# zxld383-boost-driver-mk-4_0.net
KiCad netlist of a schematic drawn in EAGLE
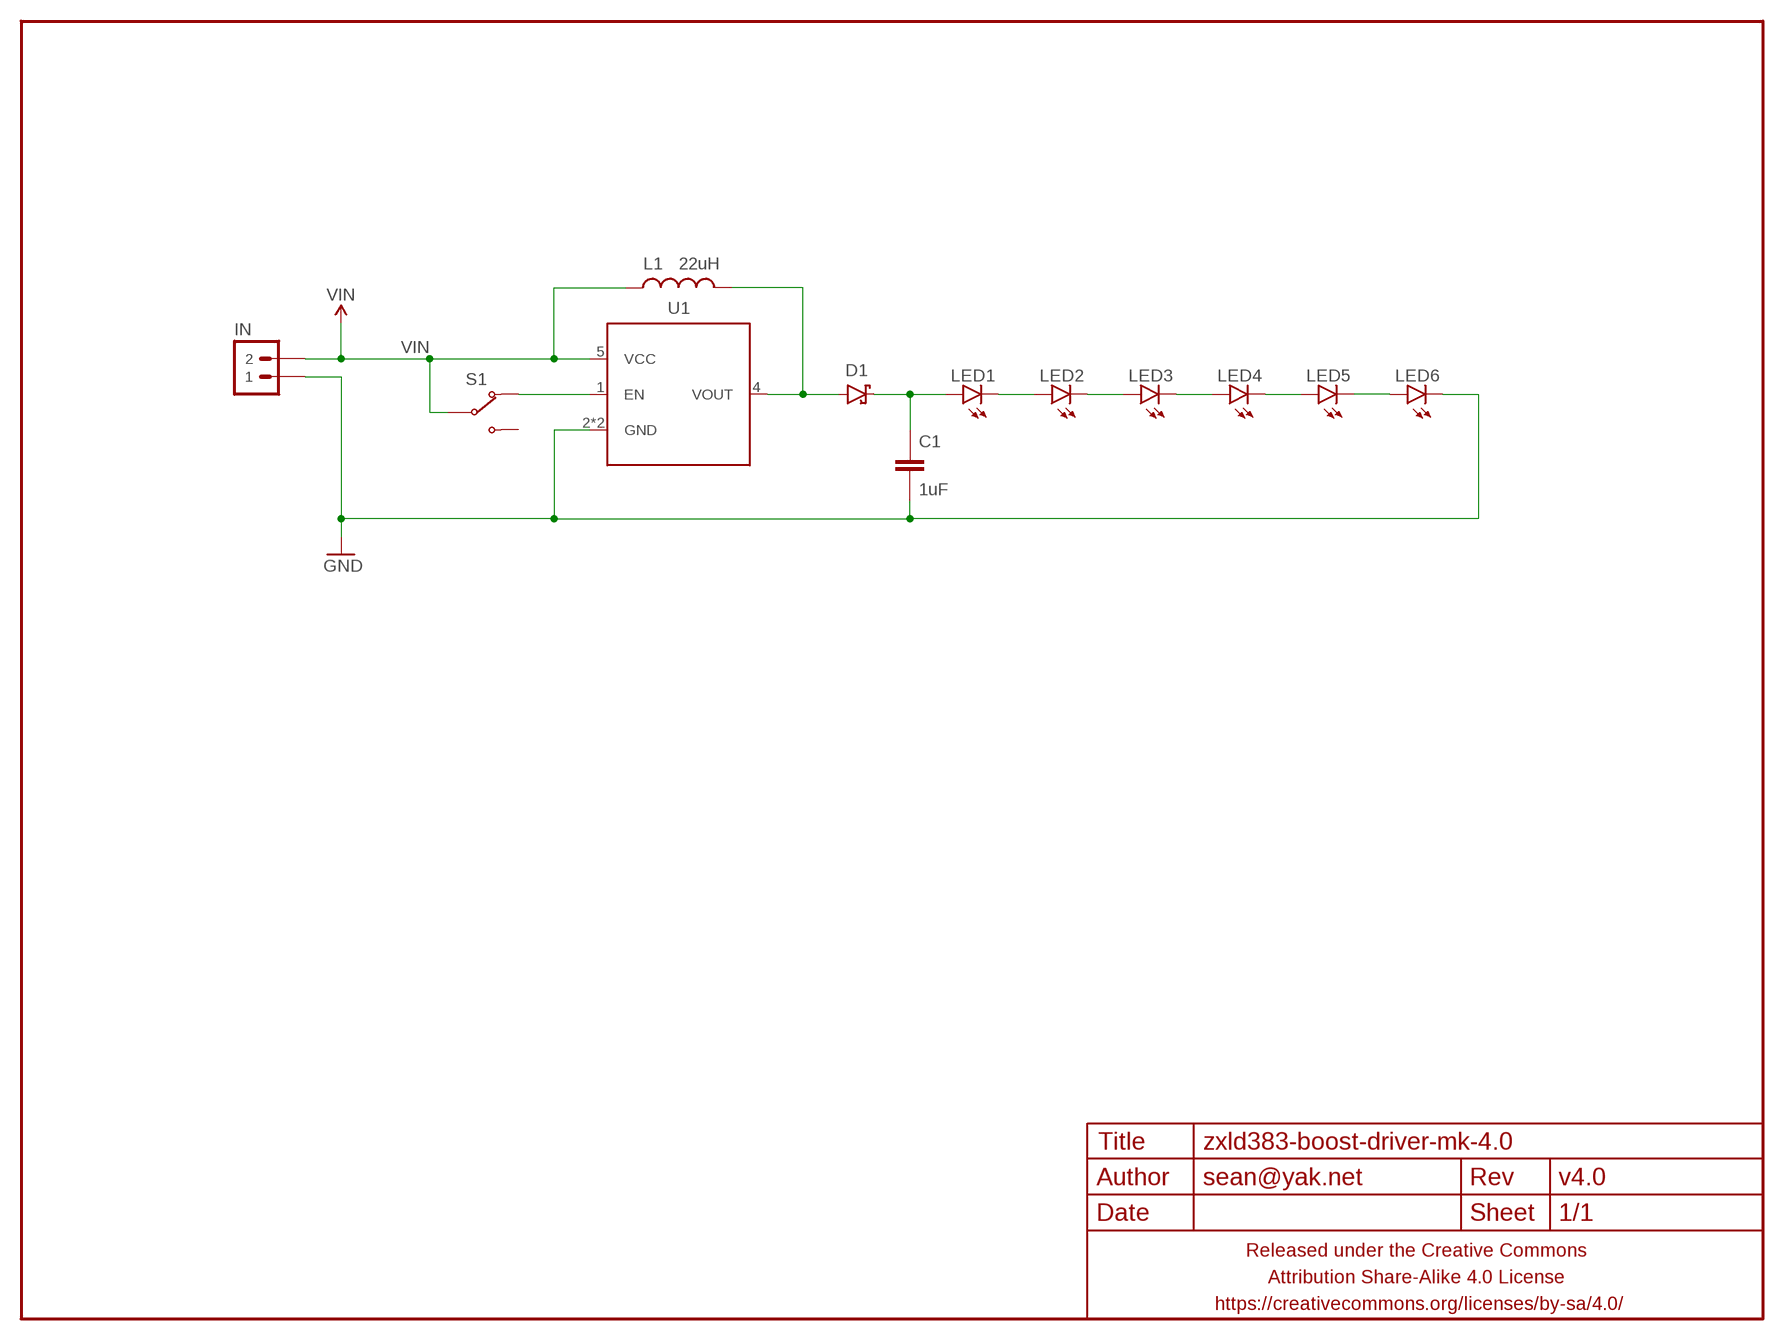
[diagram p0: schematic, sheet 1]

(export (version "E")
  (design (tool "Eeschema 10.0.6"))
  (components
    (comp (ref "C1")
      (value "1uF")
      (footprint "eagle-import:C0603-TIGHTER")
      (libsource (lib "eagle-import") (part "CAPACITOR-CERAMICC0603-TIGHTER"))
    )
    (comp (ref "D1")
      (value "DIODE-SCHOTTKYSOD323")
      (footprint "eagle-import:SOD323-SCHOTTKY")
      (libsource (lib "eagle-import") (part "DIODE-SCHOTTKYSOD323"))
    )
    (comp (ref "FRAME1")
      (value "FRAME-LETTERNO_PACKAGE")
      (footprint "eagle-import:DUMMY")
      (fields (field (name "DESIGNER") "sean@yak.net") (field (name "VERSION") "v4.0"))
      (libsource (lib "eagle-import") (part "FRAME-LETTERNO_PACKAGE"))
    )
    (comp (ref "IN")
      (value "M02PTH-CENTERED-R+")
      (footprint "eagle-import:1X02-CENTER-R+")
      (libsource (lib "eagle-import") (part "M02PTH-CENTERED-R+"))
    )
    (comp (ref "L1")
      (value "22uH")
      (footprint "eagle-import:L0603")
      (libsource (lib "eagle-import") (part "INDUCTOR0603-TIGHTER"))
    )
    (comp (ref "LED1")
      (value "LED5MM_SHORTPADS")
      (footprint "eagle-import:LED5MM_SHORTPADS")
      (libsource (lib "eagle-import") (part "LED5MM_SHORTPADS"))
    )
    (comp (ref "LED2")
      (value "LED5MM_SHORTPADS")
      (footprint "eagle-import:LED5MM_SHORTPADS")
      (libsource (lib "eagle-import") (part "LED5MM_SHORTPADS"))
    )
    (comp (ref "LED3")
      (value "LED5MM_SHORTPADS")
      (footprint "eagle-import:LED5MM_SHORTPADS")
      (libsource (lib "eagle-import") (part "LED5MM_SHORTPADS"))
    )
    (comp (ref "LED4")
      (value "LED5MM_SHORTPADS")
      (footprint "eagle-import:LED5MM_SHORTPADS")
      (libsource (lib "eagle-import") (part "LED5MM_SHORTPADS"))
    )
    (comp (ref "LED5")
      (value "LED5MM_SHORTPADS")
      (footprint "eagle-import:LED5MM_SHORTPADS")
      (libsource (lib "eagle-import") (part "LED5MM_SHORTPADS"))
    )
    (comp (ref "LED6")
      (value "LED5MM_SHORTPADS")
      (footprint "eagle-import:LED5MM_SHORTPADS")
      (libsource (lib "eagle-import") (part "LED5MM_SHORTPADS"))
    )
    (comp (ref "S1")
      (value "SWITCH-SPDTSMD-RA")
      (footprint "eagle-import:SWITCH-SPDT-SMD-RA")
      (libsource (lib "eagle-import") (part "SWITCH-SPDTSMD-RA"))
    )
    (comp (ref "U1")
      (value "ZXLD383")
      (footprint "eagle-import:TSOT-23-5")
      (libsource (lib "eagle-import") (part "ZXLD383"))
    )
  )
  (nets
    (net (code "1") (name "GND") (class "Default")
      (node (ref "C1") (pin "2") (pinfunction "2_2") (pintype "passive"))
      (node (ref "IN") (pin "1") (pinfunction "1_1") (pintype "passive"))
      (node (ref "LED6") (pin "K") (pinfunction "C_K") (pintype "passive"))
      (node (ref "U1") (pin "2") (pinfunction "GND_2") (pintype "bidirectional"))
      (node (ref "U1") (pin "3") (pinfunction "GND_3") (pintype "bidirectional"))
    )
    (net (code "2") (name "Net-(C1-Pad1)") (class "Default")
      (node (ref "C1") (pin "1") (pinfunction "1_1") (pintype "passive"))
      (node (ref "D1") (pin "C") (pinfunction "C_C") (pintype "passive"))
      (node (ref "LED1") (pin "A") (pinfunction "A_A") (pintype "passive"))
    )
    (net (code "3") (name "Net-(LED1-C)") (class "Default")
      (node (ref "LED1") (pin "K") (pinfunction "C_K") (pintype "passive"))
      (node (ref "LED2") (pin "A") (pinfunction "A_A") (pintype "passive"))
    )
    (net (code "4") (name "Net-(LED2-C)") (class "Default")
      (node (ref "LED2") (pin "K") (pinfunction "C_K") (pintype "passive"))
      (node (ref "LED3") (pin "A") (pinfunction "A_A") (pintype "passive"))
    )
    (net (code "5") (name "Net-(LED3-C)") (class "Default")
      (node (ref "LED3") (pin "K") (pinfunction "C_K") (pintype "passive"))
      (node (ref "LED4") (pin "A") (pinfunction "A_A") (pintype "passive"))
    )
    (net (code "6") (name "Net-(LED4-C)") (class "Default")
      (node (ref "LED4") (pin "K") (pinfunction "C_K") (pintype "passive"))
      (node (ref "LED5") (pin "A") (pinfunction "A_A") (pintype "passive"))
    )
    (net (code "7") (name "Net-(LED5-C)") (class "Default")
      (node (ref "LED5") (pin "K") (pinfunction "C_K") (pintype "passive"))
      (node (ref "LED6") (pin "A") (pinfunction "A_A") (pintype "passive"))
    )
    (net (code "8") (name "Net-(S1-NC)") (class "Default")
      (node (ref "S1") (pin "3") (pinfunction "NC_3") (pintype "passive"))
      (node (ref "U1") (pin "1") (pinfunction "EN_1") (pintype "bidirectional"))
    )
    (net (code "9") (name "Net-(U1-VOUT)") (class "Default")
      (node (ref "D1") (pin "A") (pinfunction "A_A") (pintype "passive"))
      (node (ref "L1") (pin "2") (pinfunction "2_2") (pintype "passive"))
      (node (ref "U1") (pin "4") (pinfunction "VOUT_4") (pintype "bidirectional"))
    )
    (net (code "10") (name "VIN") (class "Default")
      (node (ref "IN") (pin "2") (pinfunction "2_2") (pintype "passive"))
      (node (ref "L1") (pin "1") (pinfunction "1_1") (pintype "passive"))
      (node (ref "S1") (pin "2") (pinfunction "COM_2") (pintype "passive"))
      (node (ref "U1") (pin "5") (pinfunction "VCC_5") (pintype "bidirectional"))
    )
    (net (code "11") (name "unconnected-(S1-NO-Pad1)") (class "Default")
      (node (ref "S1") (pin "1") (pinfunction "NO_1") (pintype "passive"))
    )
  )
)
